# Connectors_POGOPINS.net
KiCad netlist of a schematic drawn in Altium Designer
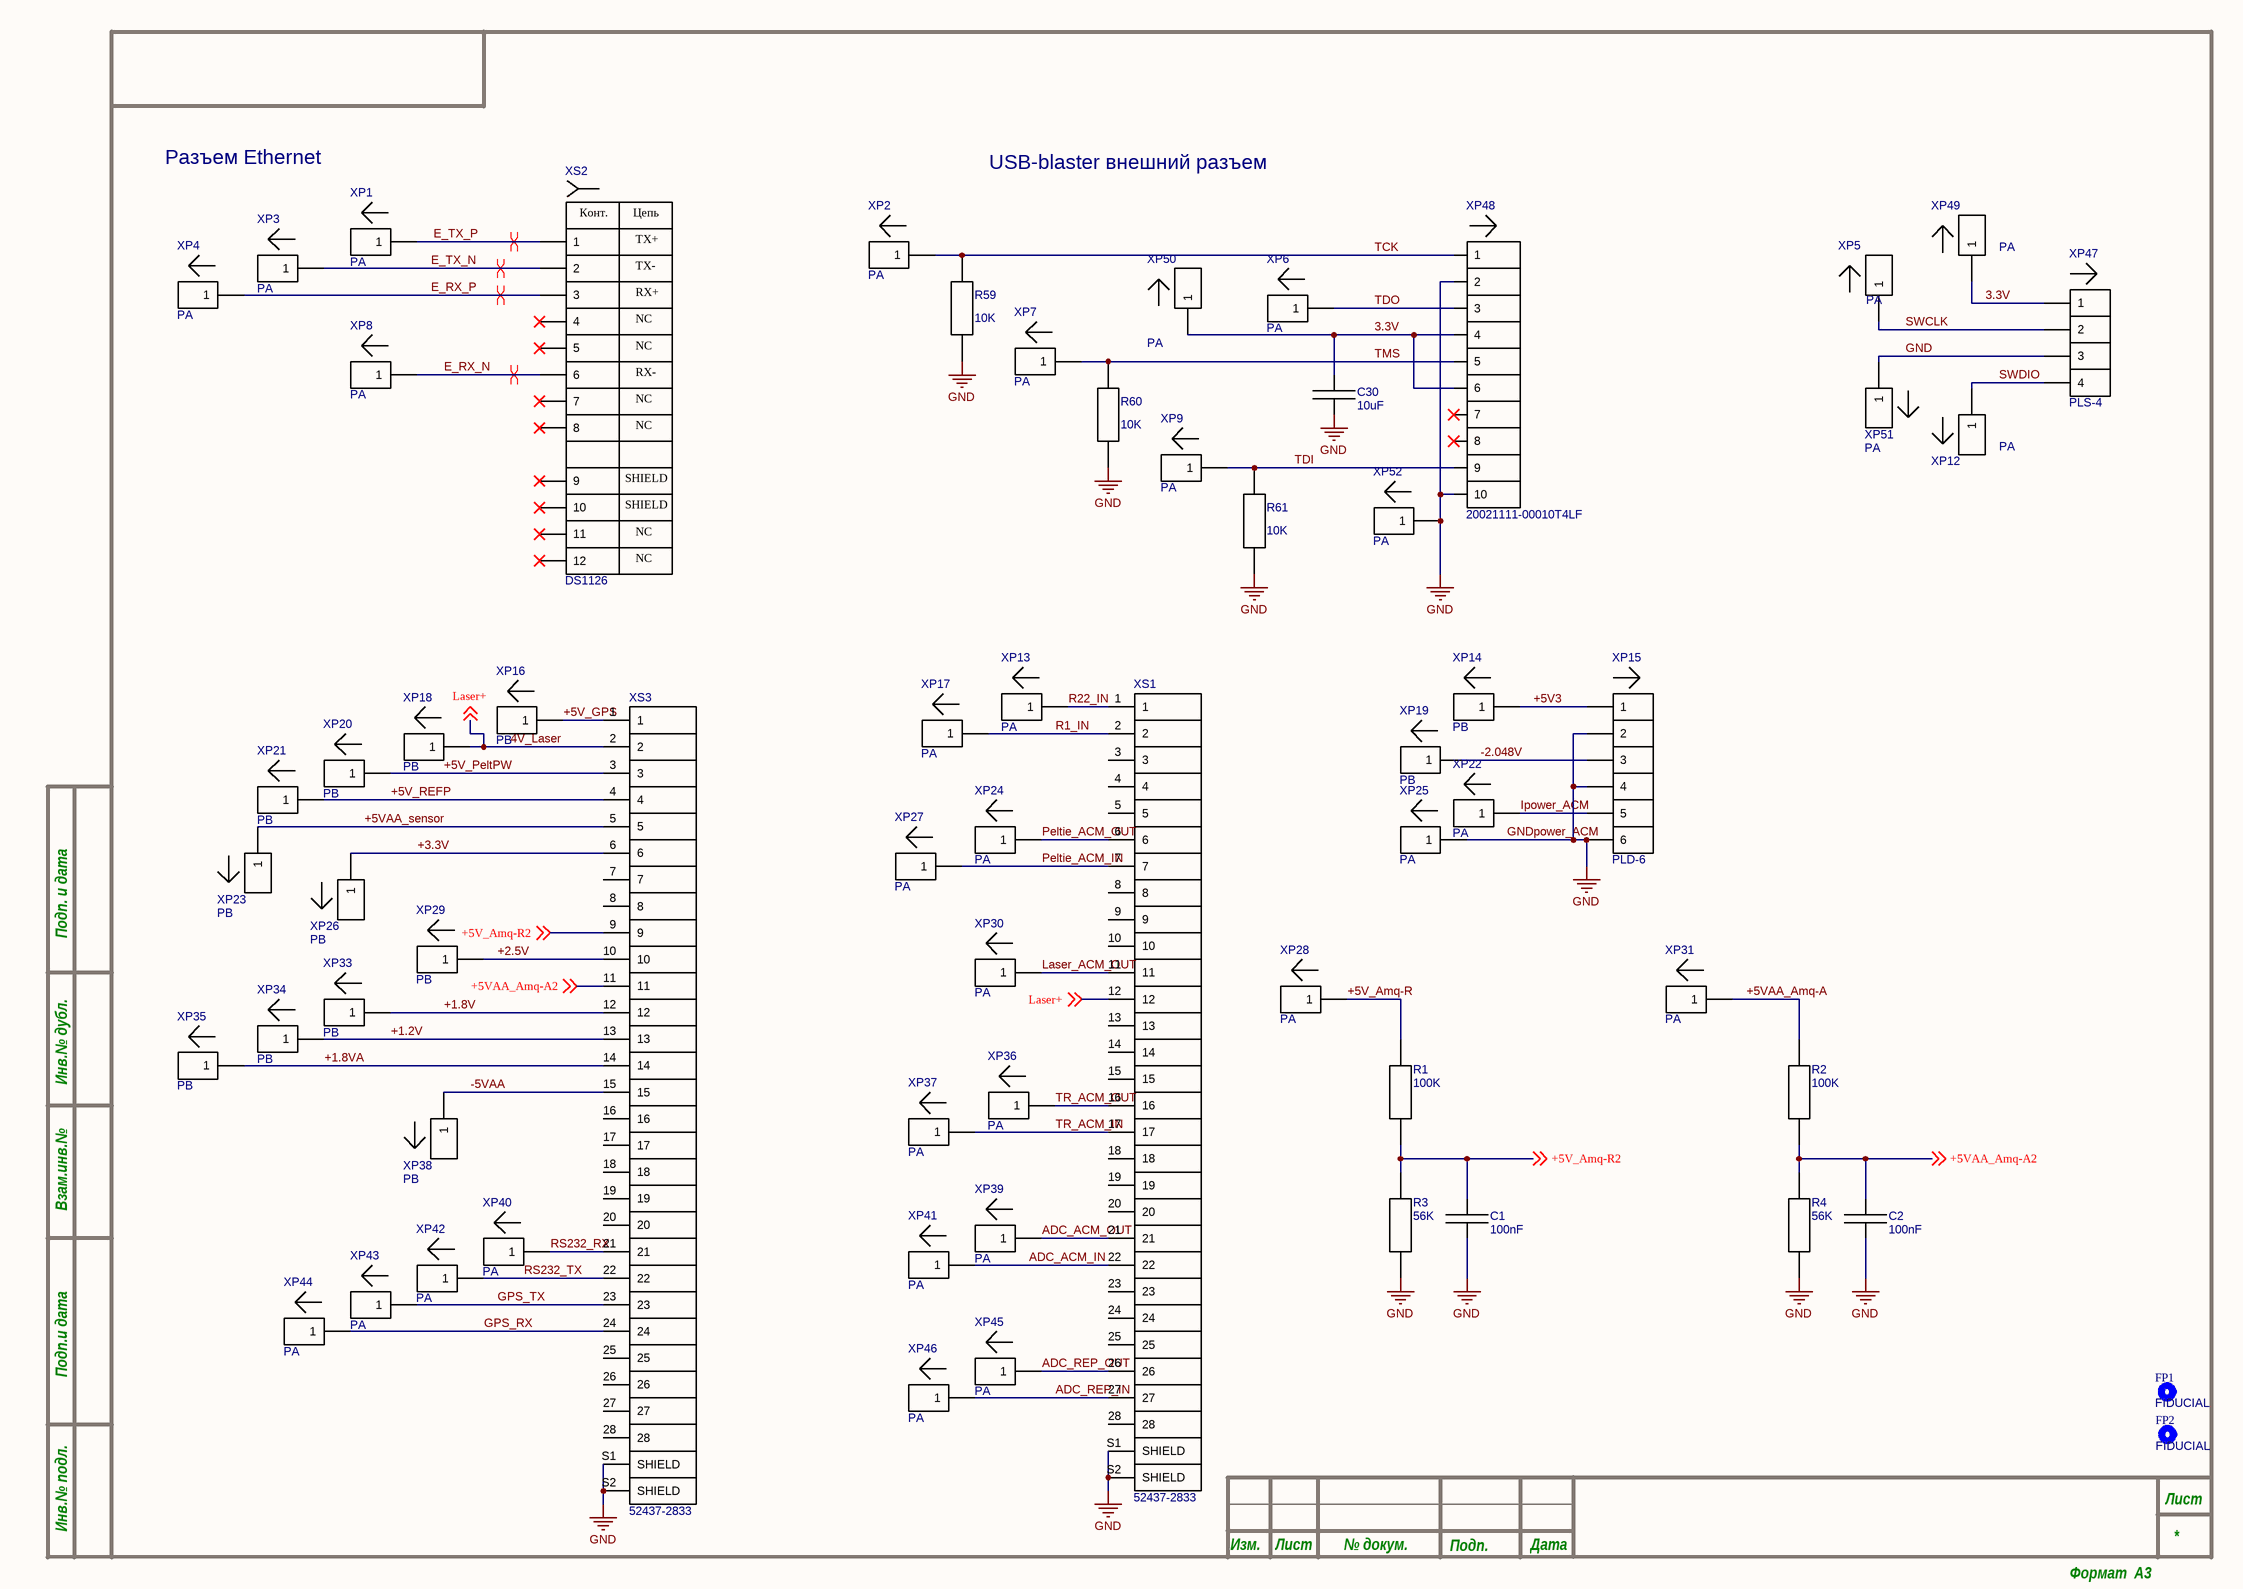
[diagram p0: Connectors — POGOPINS.SchDoc]

(export (version "E")
  (design (tool "Eeschema 10.0.6"))
  (components
    (comp (ref "C1")
      (value "100nF")
      (footprint "0402C")
      (description "C0402-100nF 10% 50V")
      (fields
        (field (name "PART NUMBER") "SMD CAP CER 100nF ±10% 50V X5R 0402")
        (field (name "ADDED_BY") "Rutel@Mail.ru")
      )
      (libsource (lib "Test_Stand_Pergam") (part "C0402-100nF 10% 50V"))
    )
    (comp (ref "C2")
      (value "100nF")
      (footprint "0402C")
      (description "C0402-100nF 10% 50V")
      (fields
        (field (name "PART NUMBER") "SMD CAP CER 100nF ±10% 50V X5R 0402")
        (field (name "ADDED_BY") "Rutel@Mail.ru")
      )
      (libsource (lib "Test_Stand_Pergam") (part "C0402-100nF 10% 50V"))
    )
    (comp (ref "C30")
      (value "10uF")
      (footprint "0402C")
      (description "C0402-10UF 10% 10V")
      (fields
        (field (name "PART NUMBER") "SMD CAP CER 10UF ±10% 10V X5R 0402")
        (field (name "ADDED_BY") "Rutel@Mail.ru")
      )
      (libsource (lib "Test_Stand_Pergam") (part "C0402-10UF 10% 10V"))
    )
    (comp (ref "FP1")
      (value "FIDUCIAL")
      (footprint "FIDICIAL POINT - R0.3")
      (fields (field (name "ADDER_BY") "ridel_av@teslatec.ru"))
      (libsource (lib "Test_Stand_Pergam") (part "FIDUCIAL_R1"))
    )
    (comp (ref "FP2")
      (value "FIDUCIAL")
      (footprint "FIDICIAL POINT - R0.3")
      (fields (field (name "ADDER_BY") "ridel_av@teslatec.ru"))
      (libsource (lib "Test_Stand_Pergam") (part "FIDUCIAL_R1"))
    )
    (comp (ref "R1")
      (value "100K")
      (footprint "R0402")
      (description "Resistor SMD 100K 1% 0402")
      (fields
        (field (name "PART NUMBER") "SMD RES 100 KOHM 1% ±100ppm/°C 0402")
        (field (name "ADDED_BY") "Rutel@teslatec.ru")
      )
      (libsource (lib "Test_Stand_Pergam") (part "R0402-100K"))
    )
    (comp (ref "R2")
      (value "100K")
      (footprint "R0402")
      (description "Resistor SMD 100K 1% 0402")
      (fields
        (field (name "PART NUMBER") "SMD RES 100 KOHM 1% ±100ppm/°C 0402")
        (field (name "ADDED_BY") "Rutel@teslatec.ru")
      )
      (libsource (lib "Test_Stand_Pergam") (part "R0402-100K"))
    )
    (comp (ref "R3")
      (value "56K")
      (footprint "R0402")
      (description "Resistor SMD 56K 1% 0402")
      (fields
        (field (name "PART NUMBER") "SMD RES 56K KOHM 1% ±100ppm/°C 0402")
        (field (name "ADDED_BY") "ridel_av@teslatec.ru")
      )
      (libsource (lib "Test_Stand_Pergam") (part "R0402-56K"))
    )
    (comp (ref "R4")
      (value "56K")
      (footprint "R0402")
      (description "Resistor SMD 56K 1% 0402")
      (fields
        (field (name "PART NUMBER") "SMD RES 56K KOHM 1% ±100ppm/°C 0402")
        (field (name "ADDED_BY") "ridel_av@teslatec.ru")
      )
      (libsource (lib "Test_Stand_Pergam") (part "R0402-56K"))
    )
    (comp (ref "R59")
      (value "10K")
      (footprint "R0402")
      (description "Resistor SMD 10K 1% 0402")
      (fields
        (field (name "PART NUMBER") "SMD RES 10 KOHM 1% ±100ppm/°C 0402")
        (field (name "ADDED_BY") "Rutel@teslatec.ru")
      )
      (libsource (lib "Test_Stand_Pergam") (part "R0402-10K"))
    )
    (comp (ref "R60")
      (value "10K")
      (footprint "R0402")
      (description "Resistor SMD 10K 1% 0402")
      (fields
        (field (name "PART NUMBER") "SMD RES 10 KOHM 1% ±100ppm/°C 0402")
        (field (name "ADDED_BY") "Rutel@teslatec.ru")
      )
      (libsource (lib "Test_Stand_Pergam") (part "R0402-10K"))
    )
    (comp (ref "R61")
      (value "10K")
      (footprint "R0402")
      (description "Resistor SMD 10K 1% 0402")
      (fields
        (field (name "PART NUMBER") "SMD RES 10 KOHM 1% ±100ppm/°C 0402")
        (field (name "ADDED_BY") "Rutel@teslatec.ru")
      )
      (libsource (lib "Test_Stand_Pergam") (part "R0402-10K"))
    )
    (comp (ref "XP1")
      (value "PA")
      (footprint "POGO PIN P100-A2/B1")
      (description "Pogo pin, 33.35x1.36")
      (fields
        (field (name "PART NUMBER") "P100-A2 / P100-A")
        (field (name "ADDED_BY") "irdolgopolowa@yandex.ru")
      )
      (libsource (lib "Test_Stand_Pergam") (part "P100-A2 / P100-A"))
    )
    (comp (ref "XP2")
      (value "PA")
      (footprint "POGO PIN P100-A2/B1")
      (description "Pogo pin, 33.35x1.36")
      (fields
        (field (name "PART NUMBER") "P100-A2 / P100-A")
        (field (name "ADDED_BY") "irdolgopolowa@yandex.ru")
      )
      (libsource (lib "Test_Stand_Pergam") (part "P100-A2 / P100-A"))
    )
    (comp (ref "XP3")
      (value "PA")
      (footprint "POGO PIN P100-A2/B1")
      (description "Pogo pin, 33.35x1.36")
      (fields
        (field (name "PART NUMBER") "P100-A2 / P100-A")
        (field (name "ADDED_BY") "irdolgopolowa@yandex.ru")
      )
      (libsource (lib "Test_Stand_Pergam") (part "P100-A2 / P100-A"))
    )
    (comp (ref "XP4")
      (value "PA")
      (footprint "POGO PIN P100-A2/B1")
      (description "Pogo pin, 33.35x1.36")
      (fields
        (field (name "PART NUMBER") "P100-A2 / P100-A")
        (field (name "ADDED_BY") "irdolgopolowa@yandex.ru")
      )
      (libsource (lib "Test_Stand_Pergam") (part "P100-A2 / P100-A"))
    )
    (comp (ref "XP5")
      (value "PA")
      (footprint "POGO PIN P100-A2/B1")
      (description "Pogo pin, 33.35x1.36")
      (fields
        (field (name "PART NUMBER") "P100-A2 / P100-A")
        (field (name "ADDED_BY") "irdolgopolowa@yandex.ru")
      )
      (libsource (lib "Test_Stand_Pergam") (part "P100-A2 / P100-A"))
    )
    (comp (ref "XP6")
      (value "PA")
      (footprint "POGO PIN P100-A2/B1")
      (description "Pogo pin, 33.35x1.36")
      (fields
        (field (name "PART NUMBER") "P100-A2 / P100-A")
        (field (name "ADDED_BY") "irdolgopolowa@yandex.ru")
      )
      (libsource (lib "Test_Stand_Pergam") (part "P100-A2 / P100-A"))
    )
    (comp (ref "XP7")
      (value "PA")
      (footprint "POGO PIN P100-A2/B1")
      (description "Pogo pin, 33.35x1.36")
      (fields
        (field (name "PART NUMBER") "P100-A2 / P100-A")
        (field (name "ADDED_BY") "irdolgopolowa@yandex.ru")
      )
      (libsource (lib "Test_Stand_Pergam") (part "P100-A2 / P100-A"))
    )
    (comp (ref "XP8")
      (value "PA")
      (footprint "POGO PIN P100-A2/B1")
      (description "Pogo pin, 33.35x1.36")
      (fields
        (field (name "PART NUMBER") "P100-A2 / P100-A")
        (field (name "ADDED_BY") "irdolgopolowa@yandex.ru")
      )
      (libsource (lib "Test_Stand_Pergam") (part "P100-A2 / P100-A"))
    )
    (comp (ref "XP9")
      (value "PA")
      (footprint "POGO PIN P100-A2/B1")
      (description "Pogo pin, 33.35x1.36")
      (fields
        (field (name "PART NUMBER") "P100-A2 / P100-A")
        (field (name "ADDED_BY") "irdolgopolowa@yandex.ru")
      )
      (libsource (lib "Test_Stand_Pergam") (part "P100-A2 / P100-A"))
    )
    (comp (ref "XP12")
      (value "PA")
      (footprint "POGO PIN P100-A2/B1")
      (description "Pogo pin, 33.35x1.36")
      (fields
        (field (name "PART NUMBER") "P100-A2 / P100-A")
        (field (name "ADDED_BY") "irdolgopolowa@yandex.ru")
      )
      (libsource (lib "Test_Stand_Pergam") (part "P100-A2 / P100-A"))
    )
    (comp (ref "XP13")
      (value "PA")
      (footprint "POGO PIN P100-A2/B1")
      (description "Pogo pin, 33.35x1.36")
      (fields
        (field (name "PART NUMBER") "P100-A2 / P100-A")
        (field (name "ADDED_BY") "irdolgopolowa@yandex.ru")
      )
      (libsource (lib "Test_Stand_Pergam") (part "P100-A2 / P100-A"))
    )
    (comp (ref "XP14")
      (value "PB")
      (footprint "POGO PIN P100-A2/B1")
      (description "Pogo pin, 33.35x1.36")
      (fields (field (name "PART NUMBER") "P100-B1") (field (name "ADDED_BY") "irdolgopolowa@yandex.ru"))
      (libsource (lib "Test_Stand_Pergam") (part "P100-B1"))
    )
    (comp (ref "XP15")
      (value "PLD-6")
      (footprint "PLD-6")
      (description "Pin Header Pitch 2.54mm")
      (fields
        (field (name "PART NUMBER") "PLD-6 (DS1021-2x3)")
        (field (name "ADDED_BY") "ponomarev_ke@teslatec.ru")
      )
      (libsource (lib "Test_Stand_Pergam") (part "PLD-6"))
    )
    (comp (ref "XP16")
      (value "PB")
      (footprint "POGO PIN P100-A2/B1")
      (description "Pogo pin, 33.35x1.36")
      (fields (field (name "PART NUMBER") "P100-B1") (field (name "ADDED_BY") "irdolgopolowa@yandex.ru"))
      (libsource (lib "Test_Stand_Pergam") (part "P100-B1"))
    )
    (comp (ref "XP17")
      (value "PA")
      (footprint "POGO PIN P100-A2/B1")
      (description "Pogo pin, 33.35x1.36")
      (fields
        (field (name "PART NUMBER") "P100-A2 / P100-A")
        (field (name "ADDED_BY") "irdolgopolowa@yandex.ru")
      )
      (libsource (lib "Test_Stand_Pergam") (part "P100-A2 / P100-A"))
    )
    (comp (ref "XP18")
      (value "PB")
      (footprint "POGO PIN P100-A2/B1")
      (description "Pogo pin, 33.35x1.36")
      (fields (field (name "PART NUMBER") "P100-B1") (field (name "ADDED_BY") "irdolgopolowa@yandex.ru"))
      (libsource (lib "Test_Stand_Pergam") (part "P100-B1"))
    )
    (comp (ref "XP19")
      (value "PB")
      (footprint "POGO PIN P100-A2/B1")
      (description "Pogo pin, 33.35x1.36")
      (fields (field (name "PART NUMBER") "P100-B1") (field (name "ADDED_BY") "irdolgopolowa@yandex.ru"))
      (libsource (lib "Test_Stand_Pergam") (part "P100-B1"))
    )
    (comp (ref "XP20")
      (value "PB")
      (footprint "POGO PIN P100-A2/B1")
      (description "Pogo pin, 33.35x1.36")
      (fields (field (name "PART NUMBER") "P100-B1") (field (name "ADDED_BY") "irdolgopolowa@yandex.ru"))
      (libsource (lib "Test_Stand_Pergam") (part "P100-B1"))
    )
    (comp (ref "XP21")
      (value "PB")
      (footprint "POGO PIN P100-A2/B1")
      (description "Pogo pin, 33.35x1.36")
      (fields (field (name "PART NUMBER") "P100-B1") (field (name "ADDED_BY") "irdolgopolowa@yandex.ru"))
      (libsource (lib "Test_Stand_Pergam") (part "P100-B1"))
    )
    (comp (ref "XP22")
      (value "PA")
      (footprint "POGO PIN P100-A2/B1")
      (description "Pogo pin, 33.35x1.36")
      (fields
        (field (name "PART NUMBER") "P100-A2 / P100-A")
        (field (name "ADDED_BY") "irdolgopolowa@yandex.ru")
      )
      (libsource (lib "Test_Stand_Pergam") (part "P100-A2 / P100-A"))
    )
    (comp (ref "XP23")
      (value "PB")
      (footprint "POGO PIN P100-A2/B1")
      (description "Pogo pin, 33.35x1.36")
      (fields (field (name "PART NUMBER") "P100-B1") (field (name "ADDED_BY") "irdolgopolowa@yandex.ru"))
      (libsource (lib "Test_Stand_Pergam") (part "P100-B1"))
    )
    (comp (ref "XP24")
      (value "PA")
      (footprint "POGO PIN P100-A2/B1")
      (description "Pogo pin, 33.35x1.36")
      (fields
        (field (name "PART NUMBER") "P100-A2 / P100-A")
        (field (name "ADDED_BY") "irdolgopolowa@yandex.ru")
      )
      (libsource (lib "Test_Stand_Pergam") (part "P100-A2 / P100-A"))
    )
    (comp (ref "XP25")
      (value "PA")
      (footprint "POGO PIN P100-A2/B1")
      (description "Pogo pin, 33.35x1.36")
      (fields
        (field (name "PART NUMBER") "P100-A2 / P100-A")
        (field (name "ADDED_BY") "irdolgopolowa@yandex.ru")
      )
      (libsource (lib "Test_Stand_Pergam") (part "P100-A2 / P100-A"))
    )
    (comp (ref "XP26")
      (value "PB")
      (footprint "POGO PIN P100-A2/B1")
      (description "Pogo pin, 33.35x1.36")
      (fields (field (name "PART NUMBER") "P100-B1") (field (name "ADDED_BY") "irdolgopolowa@yandex.ru"))
      (libsource (lib "Test_Stand_Pergam") (part "P100-B1"))
    )
    (comp (ref "XP27")
      (value "PA")
      (footprint "POGO PIN P100-A2/B1")
      (description "Pogo pin, 33.35x1.36")
      (fields
        (field (name "PART NUMBER") "P100-A2 / P100-A")
        (field (name "ADDED_BY") "irdolgopolowa@yandex.ru")
      )
      (libsource (lib "Test_Stand_Pergam") (part "P100-A2 / P100-A"))
    )
    (comp (ref "XP28")
      (value "PA")
      (footprint "POGO PIN P100-A2/B1")
      (description "Pogo pin, 33.35x1.36")
      (fields
        (field (name "PART NUMBER") "P100-A2 / P100-A")
        (field (name "ADDED_BY") "irdolgopolowa@yandex.ru")
      )
      (libsource (lib "Test_Stand_Pergam") (part "P100-A2 / P100-A"))
    )
    (comp (ref "XP29")
      (value "PB")
      (footprint "POGO PIN P100-A2/B1")
      (description "Pogo pin, 33.35x1.36")
      (fields (field (name "PART NUMBER") "P100-B1") (field (name "ADDED_BY") "irdolgopolowa@yandex.ru"))
      (libsource (lib "Test_Stand_Pergam") (part "P100-B1"))
    )
    (comp (ref "XP30")
      (value "PA")
      (footprint "POGO PIN P100-A2/B1")
      (description "Pogo pin, 33.35x1.36")
      (fields
        (field (name "PART NUMBER") "P100-A2 / P100-A")
        (field (name "ADDED_BY") "irdolgopolowa@yandex.ru")
      )
      (libsource (lib "Test_Stand_Pergam") (part "P100-A2 / P100-A"))
    )
    (comp (ref "XP31")
      (value "PA")
      (footprint "POGO PIN P100-A2/B1")
      (description "Pogo pin, 33.35x1.36")
      (fields
        (field (name "PART NUMBER") "P100-A2 / P100-A")
        (field (name "ADDED_BY") "irdolgopolowa@yandex.ru")
      )
      (libsource (lib "Test_Stand_Pergam") (part "P100-A2 / P100-A"))
    )
    (comp (ref "XP33")
      (value "PB")
      (footprint "POGO PIN P100-A2/B1")
      (description "Pogo pin, 33.35x1.36")
      (fields (field (name "PART NUMBER") "P100-B1") (field (name "ADDED_BY") "irdolgopolowa@yandex.ru"))
      (libsource (lib "Test_Stand_Pergam") (part "P100-B1"))
    )
    (comp (ref "XP34")
      (value "PB")
      (footprint "POGO PIN P100-A2/B1")
      (description "Pogo pin, 33.35x1.36")
      (fields (field (name "PART NUMBER") "P100-B1") (field (name "ADDED_BY") "irdolgopolowa@yandex.ru"))
      (libsource (lib "Test_Stand_Pergam") (part "P100-B1"))
    )
    (comp (ref "XP35")
      (value "PB")
      (footprint "POGO PIN P100-A2/B1")
      (description "Pogo pin, 33.35x1.36")
      (fields (field (name "PART NUMBER") "P100-B1") (field (name "ADDED_BY") "irdolgopolowa@yandex.ru"))
      (libsource (lib "Test_Stand_Pergam") (part "P100-B1"))
    )
    (comp (ref "XP36")
      (value "PA")
      (footprint "POGO PIN P100-A2/B1")
      (description "Pogo pin, 33.35x1.36")
      (fields
        (field (name "PART NUMBER") "P100-A2 / P100-A")
        (field (name "ADDED_BY") "irdolgopolowa@yandex.ru")
      )
      (libsource (lib "Test_Stand_Pergam") (part "P100-A2 / P100-A"))
    )
    (comp (ref "XP37")
      (value "PA")
      (footprint "POGO PIN P100-A2/B1")
      (description "Pogo pin, 33.35x1.36")
      (fields
        (field (name "PART NUMBER") "P100-A2 / P100-A")
        (field (name "ADDED_BY") "irdolgopolowa@yandex.ru")
      )
      (libsource (lib "Test_Stand_Pergam") (part "P100-A2 / P100-A"))
    )
    (comp (ref "XP38")
      (value "PB")
      (footprint "POGO PIN P100-A2/B1")
      (description "Pogo pin, 33.35x1.36")
      (fields (field (name "PART NUMBER") "P100-B1") (field (name "ADDED_BY") "irdolgopolowa@yandex.ru"))
      (libsource (lib "Test_Stand_Pergam") (part "P100-B1"))
    )
    (comp (ref "XP39")
      (value "PA")
      (footprint "POGO PIN P100-A2/B1")
      (description "Pogo pin, 33.35x1.36")
      (fields
        (field (name "PART NUMBER") "P100-A2 / P100-A")
        (field (name "ADDED_BY") "irdolgopolowa@yandex.ru")
      )
      (libsource (lib "Test_Stand_Pergam") (part "P100-A2 / P100-A"))
    )
    (comp (ref "XP40")
      (value "PA")
      (footprint "POGO PIN P100-A2/B1")
      (description "Pogo pin, 33.35x1.36")
      (fields
        (field (name "PART NUMBER") "P100-A2 / P100-A")
        (field (name "ADDED_BY") "irdolgopolowa@yandex.ru")
      )
      (libsource (lib "Test_Stand_Pergam") (part "P100-A2 / P100-A"))
    )
    (comp (ref "XP41")
      (value "PA")
      (footprint "POGO PIN P100-A2/B1")
      (description "Pogo pin, 33.35x1.36")
      (fields
        (field (name "PART NUMBER") "P100-A2 / P100-A")
        (field (name "ADDED_BY") "irdolgopolowa@yandex.ru")
      )
      (libsource (lib "Test_Stand_Pergam") (part "P100-A2 / P100-A"))
    )
    (comp (ref "XP42")
      (value "PA")
      (footprint "POGO PIN P100-A2/B1")
      (description "Pogo pin, 33.35x1.36")
      (fields
        (field (name "PART NUMBER") "P100-A2 / P100-A")
        (field (name "ADDED_BY") "irdolgopolowa@yandex.ru")
      )
      (libsource (lib "Test_Stand_Pergam") (part "P100-A2 / P100-A"))
    )
    (comp (ref "XP43")
      (value "PA")
      (footprint "POGO PIN P100-A2/B1")
      (description "Pogo pin, 33.35x1.36")
      (fields
        (field (name "PART NUMBER") "P100-A2 / P100-A")
        (field (name "ADDED_BY") "irdolgopolowa@yandex.ru")
      )
      (libsource (lib "Test_Stand_Pergam") (part "P100-A2 / P100-A"))
    )
    (comp (ref "XP44")
      (value "PA")
      (footprint "POGO PIN P100-A2/B1")
      (description "Pogo pin, 33.35x1.36")
      (fields
        (field (name "PART NUMBER") "P100-A2 / P100-A")
        (field (name "ADDED_BY") "irdolgopolowa@yandex.ru")
      )
      (libsource (lib "Test_Stand_Pergam") (part "P100-A2 / P100-A"))
    )
    (comp (ref "XP45")
      (value "PA")
      (footprint "POGO PIN P100-A2/B1")
      (description "Pogo pin, 33.35x1.36")
      (fields
        (field (name "PART NUMBER") "P100-A2 / P100-A")
        (field (name "ADDED_BY") "irdolgopolowa@yandex.ru")
      )
      (libsource (lib "Test_Stand_Pergam") (part "P100-A2 / P100-A"))
    )
    (comp (ref "XP46")
      (value "PA")
      (footprint "POGO PIN P100-A2/B1")
      (description "Pogo pin, 33.35x1.36")
      (fields
        (field (name "PART NUMBER") "P100-A2 / P100-A")
        (field (name "ADDED_BY") "irdolgopolowa@yandex.ru")
      )
      (libsource (lib "Test_Stand_Pergam") (part "P100-A2 / P100-A"))
    )
    (comp (ref "XP47")
      (value "PLS-4")
      (footprint "PLS-4")
      (description "HEADER 2.54mm")
      (fields (field (name "MATING PART") "BLS-4") (field (name "ADDED_BY") "irdolgopolowa@yandex.ru"))
      (libsource (lib "Test_Stand_Pergam") (part "PLS-4"))
    )
    (comp (ref "XP48")
      (value "20021111-00010T4LF")
      (footprint "20021111-00010T4LF")
      (description "20021111-00010T4LF. pin 10")
      (fields (field (name "ADDED_BY") "irdolgopolowa@yandex.ru"))
      (libsource (lib "Test_Stand_Pergam") (part "20021111-00010T4LF"))
    )
    (comp (ref "XP49")
      (value "PA")
      (footprint "POGO PIN P100-A2/B1")
      (description "Pogo pin, 33.35x1.36")
      (fields
        (field (name "PART NUMBER") "P100-A2 / P100-A")
        (field (name "ADDED_BY") "irdolgopolowa@yandex.ru")
      )
      (libsource (lib "Test_Stand_Pergam") (part "P100-A2 / P100-A"))
    )
    (comp (ref "XP50")
      (value "PA")
      (footprint "POGO PIN P100-A2/B1")
      (description "Pogo pin, 33.35x1.36")
      (fields
        (field (name "PART NUMBER") "P100-A2 / P100-A")
        (field (name "ADDED_BY") "irdolgopolowa@yandex.ru")
      )
      (libsource (lib "Test_Stand_Pergam") (part "P100-A2 / P100-A"))
    )
    (comp (ref "XP51")
      (value "PA")
      (footprint "POGO PIN P100-A2/B1")
      (description "Pogo pin, 33.35x1.36")
      (fields
        (field (name "PART NUMBER") "P100-A2 / P100-A")
        (field (name "ADDED_BY") "irdolgopolowa@yandex.ru")
      )
      (libsource (lib "Test_Stand_Pergam") (part "P100-A2 / P100-A"))
    )
    (comp (ref "XP52")
      (value "PA")
      (footprint "POGO PIN P100-A2/B1")
      (description "Pogo pin, 33.35x1.36")
      (fields
        (field (name "PART NUMBER") "P100-A2 / P100-A")
        (field (name "ADDED_BY") "irdolgopolowa@yandex.ru")
      )
      (libsource (lib "Test_Stand_Pergam") (part "P100-A2 / P100-A"))
    )
    (comp (ref "XS1")
      (value "52437-2833")
      (footprint "MOLEX_52437-2833")
      (description "28 Position FFC, FPC Connector Contacts, Bottom 0.020 _0.50mm_ Surface Mount, Right Angle")
      (fields
        (field (name "PART NUMBER") "52437-2833 (MOLEX)")
        (field (name "MATING PART") "FFCA 28pin, 0.5mm pitch, AVM 20624 80C 60V VW-1")
        (field (name "ADDED_BY") "ridel_av@teslatec.ru")
      )
      (libsource (lib "Test_Stand_Pergam") (part "52437-2833"))
    )
    (comp (ref "XS2")
      (value "DS1126")
      (footprint "DS1126")
      (description "Ethernet PCB 8/8 RJ45")
      (fields (field (name "ADDED_BY") "irdolgopolowa@yandex.ru"))
      (libsource (lib "Test_Stand_Pergam") (part "DS1126"))
    )
    (comp (ref "XS3")
      (value "52437-2833")
      (footprint "MOLEX_52437-2833")
      (description "28 Position FFC, FPC Connector Contacts, Bottom 0.020 _0.50mm_ Surface Mount, Right Angle")
      (fields
        (field (name "PART NUMBER") "52437-2833 (MOLEX)")
        (field (name "MATING PART") "FFCA 28pin, 0.5mm pitch, AVM 20624 80C 60V VW-1")
        (field (name "ADDED_BY") "ridel_av@teslatec.ru")
      )
      (libsource (lib "Test_Stand_Pergam") (part "52437-2833"))
    )
  )
  (nets
    (net (code "1") (name "+5VAA_Amq-A2") (class "Default")
      (node (ref "C2") (pin "2") (pinfunction "2_2") (pintype "passive"))
      (node (ref "R2") (pin "2") (pinfunction "2_2") (pintype "passive"))
      (node (ref "R4") (pin "1") (pinfunction "1_1") (pintype "passive"))
      (node (ref "XS3") (pin "11") (pinfunction "11_11") (pintype "passive"))
    )
    (net (code "2") (name "+5V_Amq-R2") (class "Default")
      (node (ref "C1") (pin "2") (pinfunction "2_2") (pintype "passive"))
      (node (ref "R1") (pin "2") (pinfunction "2_2") (pintype "passive"))
      (node (ref "R3") (pin "1") (pinfunction "1_1") (pintype "passive"))
      (node (ref "XS3") (pin "9") (pinfunction "9_9") (pintype "passive"))
    )
    (net (code "3") (name "/+1.2V") (class "Default")
      (node (ref "XP34") (pin "1") (pinfunction "1_1") (pintype "passive"))
      (node (ref "XS3") (pin "13") (pinfunction "13_13") (pintype "passive"))
    )
    (net (code "4") (name "/+1.8V") (class "Default")
      (node (ref "XP33") (pin "1") (pinfunction "1_1") (pintype "passive"))
      (node (ref "XS3") (pin "12") (pinfunction "12_12") (pintype "passive"))
    )
    (net (code "5") (name "/+1.8VA") (class "Default")
      (node (ref "XP35") (pin "1") (pinfunction "1_1") (pintype "passive"))
      (node (ref "XS3") (pin "14") (pinfunction "14_14") (pintype "passive"))
    )
    (net (code "6") (name "/+2.5V") (class "Default")
      (node (ref "XP29") (pin "1") (pinfunction "1_1") (pintype "passive"))
      (node (ref "XS3") (pin "10") (pinfunction "10_10") (pintype "passive"))
    )
    (net (code "7") (name "/+3.3V") (class "Default")
      (node (ref "XP26") (pin "1") (pinfunction "1_1") (pintype "passive"))
      (node (ref "XS3") (pin "6") (pinfunction "6_6") (pintype "passive"))
    )
    (net (code "8") (name "/+5V3") (class "Default")
      (node (ref "XP14") (pin "1") (pinfunction "1_1") (pintype "passive"))
      (node (ref "XP15") (pin "1") (pinfunction "1_1") (pintype "passive"))
    )
    (net (code "9") (name "/+5VAA_Amq-A") (class "Default")
      (node (ref "R2") (pin "1") (pinfunction "1_1") (pintype "passive"))
      (node (ref "XP31") (pin "1") (pinfunction "1_1") (pintype "passive"))
    )
    (net (code "10") (name "/+5VAA_sensor") (class "Default")
      (node (ref "XP23") (pin "1") (pinfunction "1_1") (pintype "passive"))
      (node (ref "XS3") (pin "5") (pinfunction "5_5") (pintype "passive"))
    )
    (net (code "11") (name "/+5V_Amq-R") (class "Default")
      (node (ref "R1") (pin "1") (pinfunction "1_1") (pintype "passive"))
      (node (ref "XP28") (pin "1") (pinfunction "1_1") (pintype "passive"))
    )
    (net (code "12") (name "/+5V_GPS") (class "Default")
      (node (ref "XP16") (pin "1") (pinfunction "1_1") (pintype "passive"))
      (node (ref "XS3") (pin "1") (pinfunction "1_1") (pintype "passive"))
    )
    (net (code "13") (name "/+5V_PeltPW") (class "Default")
      (node (ref "XP20") (pin "1") (pinfunction "1_1") (pintype "passive"))
      (node (ref "XS3") (pin "3") (pinfunction "3_3") (pintype "passive"))
    )
    (net (code "14") (name "/+5V_REFP") (class "Default")
      (node (ref "XP21") (pin "1") (pinfunction "1_1") (pintype "passive"))
      (node (ref "XS3") (pin "4") (pinfunction "4_4") (pintype "passive"))
    )
    (net (code "15") (name "/-2.048V") (class "Default")
      (node (ref "XP15") (pin "3") (pinfunction "3_3") (pintype "passive"))
      (node (ref "XP19") (pin "1") (pinfunction "1_1") (pintype "passive"))
    )
    (net (code "16") (name "/-5VAA") (class "Default")
      (node (ref "XP38") (pin "1") (pinfunction "1_1") (pintype "passive"))
      (node (ref "XS3") (pin "15") (pinfunction "15_15") (pintype "passive"))
    )
    (net (code "17") (name "/3.3V") (class "Default")
      (node (ref "C30") (pin "2") (pinfunction "2_2") (pintype "passive"))
      (node (ref "XP47") (pin "1") (pinfunction "1_1") (pintype "passive"))
      (node (ref "XP48") (pin "4") (pinfunction "4_4") (pintype "passive"))
      (node (ref "XP48") (pin "6") (pinfunction "6_6") (pintype "passive"))
      (node (ref "XP49") (pin "1") (pinfunction "1_1") (pintype "passive"))
      (node (ref "XP50") (pin "1") (pinfunction "1_1") (pintype "passive"))
    )
    (net (code "18") (name "/ADC_ACM_IN") (class "Default")
      (node (ref "XP41") (pin "1") (pinfunction "1_1") (pintype "passive"))
      (node (ref "XS1") (pin "22") (pinfunction "22_22") (pintype "passive"))
    )
    (net (code "19") (name "/ADC_ACM_OUT") (class "Default")
      (node (ref "XP39") (pin "1") (pinfunction "1_1") (pintype "passive"))
      (node (ref "XS1") (pin "21") (pinfunction "21_21") (pintype "passive"))
    )
    (net (code "20") (name "/ADC_REP_IN") (class "Default")
      (node (ref "XP46") (pin "1") (pinfunction "1_1") (pintype "passive"))
      (node (ref "XS1") (pin "27") (pinfunction "27_27") (pintype "passive"))
    )
    (net (code "21") (name "/ADC_REP_OUT") (class "Default")
      (node (ref "XP45") (pin "1") (pinfunction "1_1") (pintype "passive"))
      (node (ref "XS1") (pin "26") (pinfunction "26_26") (pintype "passive"))
    )
    (net (code "22") (name "/E_RX_N") (class "Default")
      (node (ref "XP8") (pin "1") (pinfunction "1_1") (pintype "passive"))
      (node (ref "XS2") (pin "6") (pinfunction "6_6") (pintype "passive"))
    )
    (net (code "23") (name "/E_RX_P") (class "Default")
      (node (ref "XP4") (pin "1") (pinfunction "1_1") (pintype "passive"))
      (node (ref "XS2") (pin "3") (pinfunction "3_3") (pintype "passive"))
    )
    (net (code "24") (name "/E_TX_N") (class "Default")
      (node (ref "XP3") (pin "1") (pinfunction "1_1") (pintype "passive"))
      (node (ref "XS2") (pin "2") (pinfunction "2_2") (pintype "passive"))
    )
    (net (code "25") (name "/E_TX_P") (class "Default")
      (node (ref "XP1") (pin "1") (pinfunction "1_1") (pintype "passive"))
      (node (ref "XS2") (pin "1") (pinfunction "1_1") (pintype "passive"))
    )
    (net (code "26") (name "/GPS_RX") (class "Default")
      (node (ref "XP44") (pin "1") (pinfunction "1_1") (pintype "passive"))
      (node (ref "XS3") (pin "24") (pinfunction "24_24") (pintype "passive"))
    )
    (net (code "27") (name "/GPS_TX") (class "Default")
      (node (ref "XP43") (pin "1") (pinfunction "1_1") (pintype "passive"))
      (node (ref "XS3") (pin "23") (pinfunction "23_23") (pintype "passive"))
    )
    (net (code "28") (name "/Ipower_ACM") (class "Default")
      (node (ref "XP15") (pin "5") (pinfunction "5_5") (pintype "passive"))
      (node (ref "XP22") (pin "1") (pinfunction "1_1") (pintype "passive"))
    )
    (net (code "29") (name "/Laser_ACM_OUT") (class "Default")
      (node (ref "XP30") (pin "1") (pinfunction "1_1") (pintype "passive"))
      (node (ref "XS1") (pin "11") (pinfunction "11_11") (pintype "passive"))
    )
    (net (code "30") (name "/Peltie_ACM_IN") (class "Default")
      (node (ref "XP27") (pin "1") (pinfunction "1_1") (pintype "passive"))
      (node (ref "XS1") (pin "7") (pinfunction "7_7") (pintype "passive"))
    )
    (net (code "31") (name "/Peltie_ACM_OUT") (class "Default")
      (node (ref "XP24") (pin "1") (pinfunction "1_1") (pintype "passive"))
      (node (ref "XS1") (pin "6") (pinfunction "6_6") (pintype "passive"))
    )
    (net (code "32") (name "/R1_IN") (class "Default")
      (node (ref "XP17") (pin "1") (pinfunction "1_1") (pintype "passive"))
      (node (ref "XS1") (pin "2") (pinfunction "2_2") (pintype "passive"))
    )
    (net (code "33") (name "/R22_IN") (class "Default")
      (node (ref "XP13") (pin "1") (pinfunction "1_1") (pintype "passive"))
      (node (ref "XS1") (pin "1") (pinfunction "1_1") (pintype "passive"))
    )
    (net (code "34") (name "/RS232_RX") (class "Default")
      (node (ref "XP40") (pin "1") (pinfunction "1_1") (pintype "passive"))
      (node (ref "XS3") (pin "21") (pinfunction "21_21") (pintype "passive"))
    )
    (net (code "35") (name "/RS232_TX") (class "Default")
      (node (ref "XP42") (pin "1") (pinfunction "1_1") (pintype "passive"))
      (node (ref "XS3") (pin "22") (pinfunction "22_22") (pintype "passive"))
    )
    (net (code "36") (name "/SWCLK") (class "Default")
      (node (ref "XP47") (pin "2") (pinfunction "2_2") (pintype "passive"))
      (node (ref "XP5") (pin "1") (pinfunction "1_1") (pintype "passive"))
    )
    (net (code "37") (name "/SWDIO") (class "Default")
      (node (ref "XP12") (pin "1") (pinfunction "1_1") (pintype "passive"))
      (node (ref "XP47") (pin "4") (pinfunction "4_4") (pintype "passive"))
    )
    (net (code "38") (name "/TCK") (class "Default")
      (node (ref "R59") (pin "2") (pinfunction "2_2") (pintype "passive"))
      (node (ref "XP2") (pin "1") (pinfunction "1_1") (pintype "passive"))
      (node (ref "XP48") (pin "1") (pinfunction "1_1") (pintype "passive"))
    )
    (net (code "39") (name "/TDI") (class "Default")
      (node (ref "R61") (pin "2") (pinfunction "2_2") (pintype "passive"))
      (node (ref "XP48") (pin "9") (pinfunction "9_9") (pintype "passive"))
      (node (ref "XP9") (pin "1") (pinfunction "1_1") (pintype "passive"))
    )
    (net (code "40") (name "/TDO") (class "Default")
      (node (ref "XP48") (pin "3") (pinfunction "3_3") (pintype "passive"))
      (node (ref "XP6") (pin "1") (pinfunction "1_1") (pintype "passive"))
    )
    (net (code "41") (name "/TMS") (class "Default")
      (node (ref "R60") (pin "2") (pinfunction "2_2") (pintype "passive"))
      (node (ref "XP48") (pin "5") (pinfunction "5_5") (pintype "passive"))
      (node (ref "XP7") (pin "1") (pinfunction "1_1") (pintype "passive"))
    )
    (net (code "42") (name "/TR_ACM_IN") (class "Default")
      (node (ref "XP37") (pin "1") (pinfunction "1_1") (pintype "passive"))
      (node (ref "XS1") (pin "17") (pinfunction "17_17") (pintype "passive"))
    )
    (net (code "43") (name "/TR_ACM_OUT") (class "Default")
      (node (ref "XP36") (pin "1") (pinfunction "1_1") (pintype "passive"))
      (node (ref "XS1") (pin "16") (pinfunction "16_16") (pintype "passive"))
    )
    (net (code "44") (name "GND") (class "Default")
      (node (ref "C1") (pin "1") (pinfunction "1_1") (pintype "passive"))
      (node (ref "C2") (pin "1") (pinfunction "1_1") (pintype "passive"))
      (node (ref "C30") (pin "1") (pinfunction "1_1") (pintype "passive"))
      (node (ref "R3") (pin "2") (pinfunction "2_2") (pintype "passive"))
      (node (ref "R4") (pin "2") (pinfunction "2_2") (pintype "passive"))
      (node (ref "R59") (pin "1") (pinfunction "1_1") (pintype "passive"))
      (node (ref "R60") (pin "1") (pinfunction "1_1") (pintype "passive"))
      (node (ref "R61") (pin "1") (pinfunction "1_1") (pintype "passive"))
      (node (ref "XP15") (pin "2") (pinfunction "2_2") (pintype "passive"))
      (node (ref "XP15") (pin "4") (pinfunction "4_4") (pintype "passive"))
      (node (ref "XP15") (pin "6") (pinfunction "6_6") (pintype "passive"))
      (node (ref "XP25") (pin "1") (pinfunction "1_1") (pintype "passive"))
      (node (ref "XP47") (pin "3") (pinfunction "3_3") (pintype "passive"))
      (node (ref "XP48") (pin "10") (pinfunction "10_10") (pintype "passive"))
      (node (ref "XP48") (pin "2") (pinfunction "2_2") (pintype "passive"))
      (node (ref "XP51") (pin "1") (pinfunction "1_1") (pintype "passive"))
      (node (ref "XP52") (pin "1") (pinfunction "1_1") (pintype "passive"))
      (node (ref "XS1") (pin "S1") (pinfunction "SHIELD_S1") (pintype "passive"))
      (node (ref "XS1") (pin "S2") (pinfunction "SHIELD_S2") (pintype "passive"))
      (node (ref "XS3") (pin "S1") (pinfunction "SHIELD_S1") (pintype "passive"))
      (node (ref "XS3") (pin "S2") (pinfunction "SHIELD_S2") (pintype "passive"))
    )
    (net (code "45") (name "Laser+") (class "Default")
      (node (ref "XP18") (pin "1") (pinfunction "1_1") (pintype "passive"))
      (node (ref "XS1") (pin "12") (pinfunction "12_12") (pintype "passive"))
      (node (ref "XS3") (pin "2") (pinfunction "2_2") (pintype "passive"))
    )
    (net (code "46") (name "unconnected-(XP48-Pad7)") (class "Default")
      (node (ref "XP48") (pin "7") (pinfunction "7_7") (pintype "passive+no_connect"))
    )
    (net (code "47") (name "unconnected-(XP48-Pad8)") (class "Default")
      (node (ref "XP48") (pin "8") (pinfunction "8_8") (pintype "passive+no_connect"))
    )
    (net (code "48") (name "unconnected-(XS1-Pad3)") (class "Default")
      (node (ref "XS1") (pin "3") (pinfunction "3_3") (pintype "passive"))
    )
    (net (code "49") (name "unconnected-(XS1-Pad4)") (class "Default")
      (node (ref "XS1") (pin "4") (pinfunction "4_4") (pintype "passive"))
    )
    (net (code "50") (name "unconnected-(XS1-Pad5)") (class "Default")
      (node (ref "XS1") (pin "5") (pinfunction "5_5") (pintype "passive"))
    )
    (net (code "51") (name "unconnected-(XS1-Pad8)") (class "Default")
      (node (ref "XS1") (pin "8") (pinfunction "8_8") (pintype "passive"))
    )
    (net (code "52") (name "unconnected-(XS1-Pad9)") (class "Default")
      (node (ref "XS1") (pin "9") (pinfunction "9_9") (pintype "passive"))
    )
    (net (code "53") (name "unconnected-(XS1-Pad10)") (class "Default")
      (node (ref "XS1") (pin "10") (pinfunction "10_10") (pintype "passive"))
    )
    (net (code "54") (name "unconnected-(XS1-Pad13)") (class "Default")
      (node (ref "XS1") (pin "13") (pinfunction "13_13") (pintype "passive"))
    )
    (net (code "55") (name "unconnected-(XS1-Pad14)") (class "Default")
      (node (ref "XS1") (pin "14") (pinfunction "14_14") (pintype "passive"))
    )
    (net (code "56") (name "unconnected-(XS1-Pad15)") (class "Default")
      (node (ref "XS1") (pin "15") (pinfunction "15_15") (pintype "passive"))
    )
    (net (code "57") (name "unconnected-(XS1-Pad18)") (class "Default")
      (node (ref "XS1") (pin "18") (pinfunction "18_18") (pintype "passive"))
    )
    (net (code "58") (name "unconnected-(XS1-Pad19)") (class "Default")
      (node (ref "XS1") (pin "19") (pinfunction "19_19") (pintype "passive"))
    )
    (net (code "59") (name "unconnected-(XS1-Pad20)") (class "Default")
      (node (ref "XS1") (pin "20") (pinfunction "20_20") (pintype "passive"))
    )
    (net (code "60") (name "unconnected-(XS1-Pad23)") (class "Default")
      (node (ref "XS1") (pin "23") (pinfunction "23_23") (pintype "passive"))
    )
    (net (code "61") (name "unconnected-(XS1-Pad24)") (class "Default")
      (node (ref "XS1") (pin "24") (pinfunction "24_24") (pintype "passive"))
    )
    (net (code "62") (name "unconnected-(XS1-Pad25)") (class "Default")
      (node (ref "XS1") (pin "25") (pinfunction "25_25") (pintype "passive"))
    )
    (net (code "63") (name "unconnected-(XS1-Pad28)") (class "Default")
      (node (ref "XS1") (pin "28") (pinfunction "28_28") (pintype "passive"))
    )
    (net (code "64") (name "unconnected-(XS2-Pad4)") (class "Default")
      (node (ref "XS2") (pin "4") (pinfunction "4_4") (pintype "passive+no_connect"))
    )
    (net (code "65") (name "unconnected-(XS2-Pad5)") (class "Default")
      (node (ref "XS2") (pin "5") (pinfunction "5_5") (pintype "passive+no_connect"))
    )
    (net (code "66") (name "unconnected-(XS2-Pad7)") (class "Default")
      (node (ref "XS2") (pin "7") (pinfunction "7_7") (pintype "passive+no_connect"))
    )
    (net (code "67") (name "unconnected-(XS2-Pad8)") (class "Default")
      (node (ref "XS2") (pin "8") (pinfunction "8_8") (pintype "passive+no_connect"))
    )
    (net (code "68") (name "unconnected-(XS2-Pad9)") (class "Default")
      (node (ref "XS2") (pin "9") (pinfunction "9_9") (pintype "passive+no_connect"))
    )
    (net (code "69") (name "unconnected-(XS2-Pad10)") (class "Default")
      (node (ref "XS2") (pin "10") (pinfunction "10_10") (pintype "passive+no_connect"))
    )
    (net (code "70") (name "unconnected-(XS2-Pad11)") (class "Default")
      (node (ref "XS2") (pin "11") (pinfunction "11_11") (pintype "passive+no_connect"))
    )
    (net (code "71") (name "unconnected-(XS2-Pad12)") (class "Default")
      (node (ref "XS2") (pin "12") (pinfunction "12_12") (pintype "passive+no_connect"))
    )
    (net (code "72") (name "unconnected-(XS3-Pad7)") (class "Default")
      (node (ref "XS3") (pin "7") (pinfunction "7_7") (pintype "passive"))
    )
    (net (code "73") (name "unconnected-(XS3-Pad8)") (class "Default")
      (node (ref "XS3") (pin "8") (pinfunction "8_8") (pintype "passive"))
    )
    (net (code "74") (name "unconnected-(XS3-Pad16)") (class "Default")
      (node (ref "XS3") (pin "16") (pinfunction "16_16") (pintype "passive"))
    )
    (net (code "75") (name "unconnected-(XS3-Pad17)") (class "Default")
      (node (ref "XS3") (pin "17") (pinfunction "17_17") (pintype "passive"))
    )
    (net (code "76") (name "unconnected-(XS3-Pad18)") (class "Default")
      (node (ref "XS3") (pin "18") (pinfunction "18_18") (pintype "passive"))
    )
    (net (code "77") (name "unconnected-(XS3-Pad19)") (class "Default")
      (node (ref "XS3") (pin "19") (pinfunction "19_19") (pintype "passive"))
    )
    (net (code "78") (name "unconnected-(XS3-Pad20)") (class "Default")
      (node (ref "XS3") (pin "20") (pinfunction "20_20") (pintype "passive"))
    )
    (net (code "79") (name "unconnected-(XS3-Pad25)") (class "Default")
      (node (ref "XS3") (pin "25") (pinfunction "25_25") (pintype "passive"))
    )
    (net (code "80") (name "unconnected-(XS3-Pad26)") (class "Default")
      (node (ref "XS3") (pin "26") (pinfunction "26_26") (pintype "passive"))
    )
    (net (code "81") (name "unconnected-(XS3-Pad27)") (class "Default")
      (node (ref "XS3") (pin "27") (pinfunction "27_27") (pintype "passive"))
    )
    (net (code "82") (name "unconnected-(XS3-Pad28)") (class "Default")
      (node (ref "XS3") (pin "28") (pinfunction "28_28") (pintype "passive"))
    )
  )
)
